# blinky.net
KiCad netlist of a schematic drawn in EAGLE
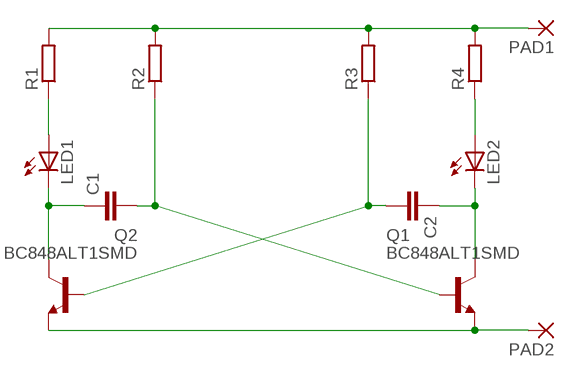
[diagram p0: schematic, sheet 1]

(export (version "E")
  (design (tool "Eeschema 10.0.6"))
  (components
    (comp (ref "C1")
      (value "C-EUC0805")
      (footprint "eagle-import:C0805")
      (libsource (lib "eagle-import") (part "C-EUC0805"))
    )
    (comp (ref "C2")
      (value "C-EUC0805")
      (footprint "eagle-import:C0805")
      (libsource (lib "eagle-import") (part "C-EUC0805"))
    )
    (comp (ref "LED1")
      (value "LEDCHIP-LED0805")
      (footprint "eagle-import:CHIP-LED0805")
      (libsource (lib "eagle-import") (part "LEDCHIP-LED0805"))
    )
    (comp (ref "LED2")
      (value "LEDCHIP-LED0805")
      (footprint "eagle-import:CHIP-LED0805")
      (libsource (lib "eagle-import") (part "LEDCHIP-LED0805"))
    )
    (comp (ref "PAD1")
      (value "2,54/1,0")
      (footprint "eagle-import:2,54_1,0")
      (libsource (lib "eagle-import") (part "2,54/1,0"))
    )
    (comp (ref "PAD2")
      (value "2,54/1,0")
      (footprint "eagle-import:2,54_1,0")
      (libsource (lib "eagle-import") (part "2,54/1,0"))
    )
    (comp (ref "Q1")
      (value "BC848ALT1SMD")
      (footprint "eagle-import:SOT23")
      (libsource (lib "eagle-import") (part "BC848SMDALT1"))
    )
    (comp (ref "Q2")
      (value "BC848ALT1SMD")
      (footprint "eagle-import:SOT23")
      (libsource (lib "eagle-import") (part "BC848SMDALT1"))
    )
    (comp (ref "R1")
      (value "R-EU_R0805")
      (footprint "eagle-import:R0805")
      (libsource (lib "eagle-import") (part "R-EU_R0805"))
    )
    (comp (ref "R2")
      (value "R-EU_R0805")
      (footprint "eagle-import:R0805")
      (libsource (lib "eagle-import") (part "R-EU_R0805"))
    )
    (comp (ref "R3")
      (value "R-EU_R0805")
      (footprint "eagle-import:R0805")
      (libsource (lib "eagle-import") (part "R-EU_R0805"))
    )
    (comp (ref "R4")
      (value "R-EU_R0805")
      (footprint "eagle-import:R0805")
      (libsource (lib "eagle-import") (part "R-EU_R0805"))
    )
  )
  (nets
    (net (code "1") (name "Net-(LED1-PadA)") (class "Default")
      (node (ref "LED1") (pin "A") (pinfunction "A_A") (pintype "passive"))
      (node (ref "R1") (pin "1") (pinfunction "1_1") (pintype "passive"))
    )
    (net (code "2") (name "Net-(LED2-PadA)") (class "Default")
      (node (ref "LED2") (pin "A") (pinfunction "A_A") (pintype "passive"))
      (node (ref "R4") (pin "1") (pinfunction "1_1") (pintype "passive"))
    )
    (net (code "3") (name "Net-(PAD1-P)") (class "Default")
      (node (ref "PAD1") (pin "1") (pinfunction "P_1") (pintype "passive"))
      (node (ref "R1") (pin "2") (pinfunction "2_2") (pintype "passive"))
      (node (ref "R2") (pin "2") (pinfunction "2_2") (pintype "passive"))
      (node (ref "R3") (pin "2") (pinfunction "2_2") (pintype "passive"))
      (node (ref "R4") (pin "2") (pinfunction "2_2") (pintype "passive"))
    )
    (net (code "4") (name "Net-(PAD2-P)") (class "Default")
      (node (ref "PAD2") (pin "1") (pinfunction "P_1") (pintype "passive"))
      (node (ref "Q1") (pin "2") (pinfunction "E_2") (pintype "passive"))
      (node (ref "Q2") (pin "2") (pinfunction "E_2") (pintype "passive"))
    )
    (net (code "5") (name "Net-(Q1-B)") (class "Default")
      (node (ref "C1") (pin "2") (pinfunction "2_2") (pintype "passive"))
      (node (ref "Q1") (pin "1") (pinfunction "B_1") (pintype "passive"))
      (node (ref "R2") (pin "1") (pinfunction "1_1") (pintype "passive"))
    )
    (net (code "6") (name "Net-(Q1-C)") (class "Default")
      (node (ref "C2") (pin "1") (pinfunction "1_1") (pintype "passive"))
      (node (ref "LED2") (pin "C") (pinfunction "C_C") (pintype "passive"))
      (node (ref "Q1") (pin "3") (pinfunction "C_3") (pintype "passive"))
    )
    (net (code "7") (name "Net-(Q2-B)") (class "Default")
      (node (ref "C2") (pin "2") (pinfunction "2_2") (pintype "passive"))
      (node (ref "Q2") (pin "1") (pinfunction "B_1") (pintype "passive"))
      (node (ref "R3") (pin "1") (pinfunction "1_1") (pintype "passive"))
    )
    (net (code "8") (name "Net-(Q2-C)") (class "Default")
      (node (ref "C1") (pin "1") (pinfunction "1_1") (pintype "passive"))
      (node (ref "LED1") (pin "C") (pinfunction "C_C") (pintype "passive"))
      (node (ref "Q2") (pin "3") (pinfunction "C_3") (pintype "passive"))
    )
  )
)
